# 301_Sensor.net
KiCad netlist of a schematic drawn in Altium Designer
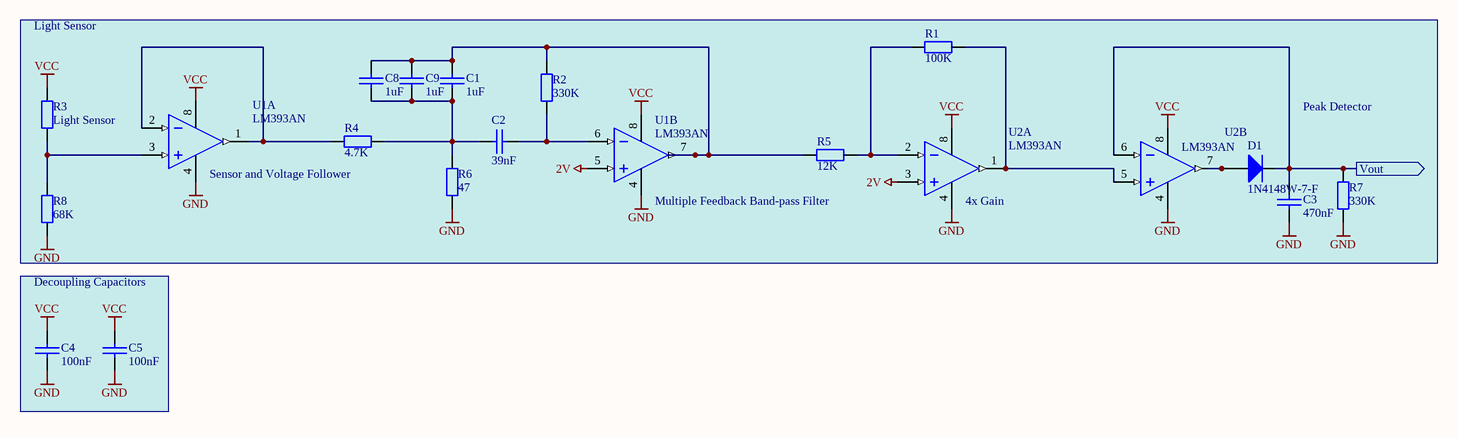
[diagram p0: 301_Sensor.SchDoc]

(export (version "E")
  (design (tool "Eeschema 10.0.6"))
  (components
    (comp (ref "C1")
      (value "1uF")
      (footprint "ece-CC2012-0805")
      (description "SM capacitor")
      (libsource (lib "ece components") (part "CAP SM0805"))
    )
    (comp (ref "C2")
      (value "39nF")
      (footprint "ece-CC2012-0805")
      (description "SM capacitor")
      (libsource (lib "ece components") (part "CAP SM0805"))
    )
    (comp (ref "C3")
      (value "470nF")
      (footprint "ece-CC2012-0805")
      (description "SM capacitor")
      (libsource (lib "ece components") (part "CAP SM0805"))
    )
    (comp (ref "C4")
      (value "100nF")
      (footprint "ece-RAD0.2")
      (description "Capacitor Non Polarised Through Hole")
      (libsource (lib "ece components") (part "CAP"))
    )
    (comp (ref "C5")
      (value "100nF")
      (footprint "ece-RAD0.2")
      (description "Capacitor Non Polarised Through Hole")
      (libsource (lib "ece components") (part "CAP"))
    )
    (comp (ref "C8")
      (value "1uF")
      (footprint "ece-CC2012-0805")
      (description "SM capacitor")
      (libsource (lib "ece components") (part "CAP SM0805"))
    )
    (comp (ref "C9")
      (value "1uF")
      (footprint "ece-CC2012-0805")
      (description "SM capacitor")
      (libsource (lib "ece components") (part "CAP SM0805"))
    )
    (comp (ref "D1")
      (value "1N4148W-7-F")
      (footprint "SOD123")
      (description "DIODE GEN PURP 100V 300MA SOD123")
      (fields
        (field (name "MANUFACTURER") "Diodes Incorporated")
        (field (name "MANUFACTURER PART NUMBER") "1N4148W-13-F")
      )
      (libsource (lib "EE209V2") (part "SMT-Diode 1N4148W-7-F"))
    )
    (comp (ref "R1")
      (value "100K")
      (footprint "RESC2012-0805SM")
      (description "SM resistor")
      (libsource (lib "") (part "Res SM 0805_1"))
    )
    (comp (ref "R2")
      (value "330K")
      (footprint "RESC2012-0805SM")
      (description "SM resistor")
      (libsource (lib "ece components") (part "Res SM 0805"))
    )
    (comp (ref "R3")
      (value "Light Sensor")
      (footprint "RESC2012-0805SM")
      (description "SM resistor")
      (libsource (lib "ece components") (part "Res SM 0805"))
    )
    (comp (ref "R4")
      (value "4.7K")
      (footprint "RESC2012-0805SM")
      (description "SM resistor")
      (libsource (lib "") (part "Res SM 0805_1"))
    )
    (comp (ref "R5")
      (value "12K")
      (footprint "RESC2012-0805SM")
      (description "SM resistor")
      (libsource (lib "") (part "Res SM 0805_2"))
    )
    (comp (ref "R6")
      (value "47")
      (footprint "RESC2012-0805SM")
      (description "SM resistor")
      (libsource (lib "ece components") (part "Res SM 0805"))
    )
    (comp (ref "R7")
      (value "330K")
      (footprint "RESC2012-0805SM")
      (description "SM resistor")
      (libsource (lib "ece components") (part "Res SM 0805"))
    )
    (comp (ref "R8")
      (value "68K")
      (footprint "RESC2012-0805SM")
      (description "SM resistor")
      (libsource (lib "ece components") (part "Res SM 0805"))
    )
    (comp (ref "U1")
      (value "LM393AN")
      (footprint "ECE-DIP8")
      (description "Dual Comparator")
      (fields (field (name "PUBLISHER") "Altium Limited"))
      (libsource (lib "ece components") (part "LM393AN"))
    )
    (comp (ref "U2")
      (value "LM393AN")
      (footprint "ECE-DIP8")
      (description "Dual Comparator")
      (fields (field (name "PUBLISHER") "Altium Limited"))
      (libsource (lib "ece components") (part "LM393AN"))
    )
  )
  (nets
    (net (code "1") (name "/Vout") (class "Default")
      (node (ref "C3") (pin "1") (pinfunction "1_1") (pintype "passive"))
      (node (ref "D1") (pin "2") (pinfunction "K_2") (pintype "passive"))
      (node (ref "R7") (pin "2") (pinfunction "2_2") (pintype "passive"))
      (node (ref "U2") (pin "6") (pinfunction "IN-_6") (pintype "input"))
    )
    (net (code "2") (name "2V") (class "Default")
      (node (ref "U1") (pin "5") (pinfunction "IN+_5") (pintype "input"))
      (node (ref "U2") (pin "3") (pinfunction "IN+_3") (pintype "input"))
    )
    (net (code "3") (name "GND") (class "Default")
      (node (ref "C3") (pin "2") (pinfunction "2_2") (pintype "passive"))
      (node (ref "C4") (pin "2") (pinfunction "2_2") (pintype "passive"))
      (node (ref "C5") (pin "2") (pinfunction "2_2") (pintype "passive"))
      (node (ref "R6") (pin "1") (pinfunction "1_1") (pintype "passive"))
      (node (ref "R7") (pin "1") (pinfunction "1_1") (pintype "passive"))
      (node (ref "R8") (pin "1") (pinfunction "1_1") (pintype "passive"))
      (node (ref "U1") (pin "4") (pinfunction "GND_4") (pintype "power_in"))
      (node (ref "U2") (pin "4") (pinfunction "GND_4") (pintype "power_in"))
    )
    (net (code "4") (name "Net-(C1-Pad2)") (class "Default")
      (node (ref "C1") (pin "2") (pinfunction "2_2") (pintype "passive"))
      (node (ref "C2") (pin "1") (pinfunction "1_1") (pintype "passive"))
      (node (ref "C8") (pin "2") (pinfunction "2_2") (pintype "passive"))
      (node (ref "C9") (pin "2") (pinfunction "2_2") (pintype "passive"))
      (node (ref "R4") (pin "2") (pinfunction "2_2") (pintype "passive"))
      (node (ref "R6") (pin "2") (pinfunction "2_2") (pintype "passive"))
    )
    (net (code "5") (name "Net-(D1-A)") (class "Default")
      (node (ref "D1") (pin "1") (pinfunction "A_1") (pintype "passive"))
      (node (ref "U2") (pin "7") (pinfunction "OUT_7") (pintype "output"))
    )
    (net (code "6") (name "Net-(U1A-IN+)") (class "Default")
      (node (ref "R3") (pin "1") (pinfunction "1_1") (pintype "passive"))
      (node (ref "R8") (pin "2") (pinfunction "2_2") (pintype "passive"))
      (node (ref "U1") (pin "3") (pinfunction "IN+_3") (pintype "input"))
    )
    (net (code "7") (name "Net-(U1A-IN-)") (class "Default")
      (node (ref "R4") (pin "1") (pinfunction "1_1") (pintype "passive"))
      (node (ref "U1") (pin "1") (pinfunction "OUT_1") (pintype "output"))
      (node (ref "U1") (pin "2") (pinfunction "IN-_2") (pintype "input"))
    )
    (net (code "8") (name "Net-(U1B-IN-)") (class "Default")
      (node (ref "C2") (pin "2") (pinfunction "2_2") (pintype "passive"))
      (node (ref "R2") (pin "1") (pinfunction "1_1") (pintype "passive"))
      (node (ref "U1") (pin "6") (pinfunction "IN-_6") (pintype "input"))
    )
    (net (code "9") (name "Net-(U1B-OUT)") (class "Default")
      (node (ref "C1") (pin "1") (pinfunction "1_1") (pintype "passive"))
      (node (ref "C8") (pin "1") (pinfunction "1_1") (pintype "passive"))
      (node (ref "C9") (pin "1") (pinfunction "1_1") (pintype "passive"))
      (node (ref "R2") (pin "2") (pinfunction "2_2") (pintype "passive"))
      (node (ref "R5") (pin "2") (pinfunction "2_2") (pintype "passive"))
      (node (ref "U1") (pin "7") (pinfunction "OUT_7") (pintype "output"))
    )
    (net (code "10") (name "Net-(U2A-IN-)") (class "Default")
      (node (ref "R1") (pin "1") (pinfunction "1_1") (pintype "passive"))
      (node (ref "R5") (pin "1") (pinfunction "1_1") (pintype "passive"))
      (node (ref "U2") (pin "2") (pinfunction "IN-_2") (pintype "input"))
    )
    (net (code "11") (name "Net-(U2A-OUT)") (class "Default")
      (node (ref "R1") (pin "2") (pinfunction "2_2") (pintype "passive"))
      (node (ref "U2") (pin "1") (pinfunction "OUT_1") (pintype "output"))
      (node (ref "U2") (pin "5") (pinfunction "IN+_5") (pintype "input"))
    )
    (net (code "12") (name "VCC") (class "Default")
      (node (ref "C4") (pin "1") (pinfunction "1_1") (pintype "passive"))
      (node (ref "C5") (pin "1") (pinfunction "1_1") (pintype "passive"))
      (node (ref "R3") (pin "2") (pinfunction "2_2") (pintype "passive"))
      (node (ref "U1") (pin "8") (pinfunction "V+_8") (pintype "power_in"))
      (node (ref "U2") (pin "8") (pinfunction "V+_8") (pintype "power_in"))
    )
  )
)
